# Sheet1.net
KiCad netlist of a schematic drawn in Altium Designer
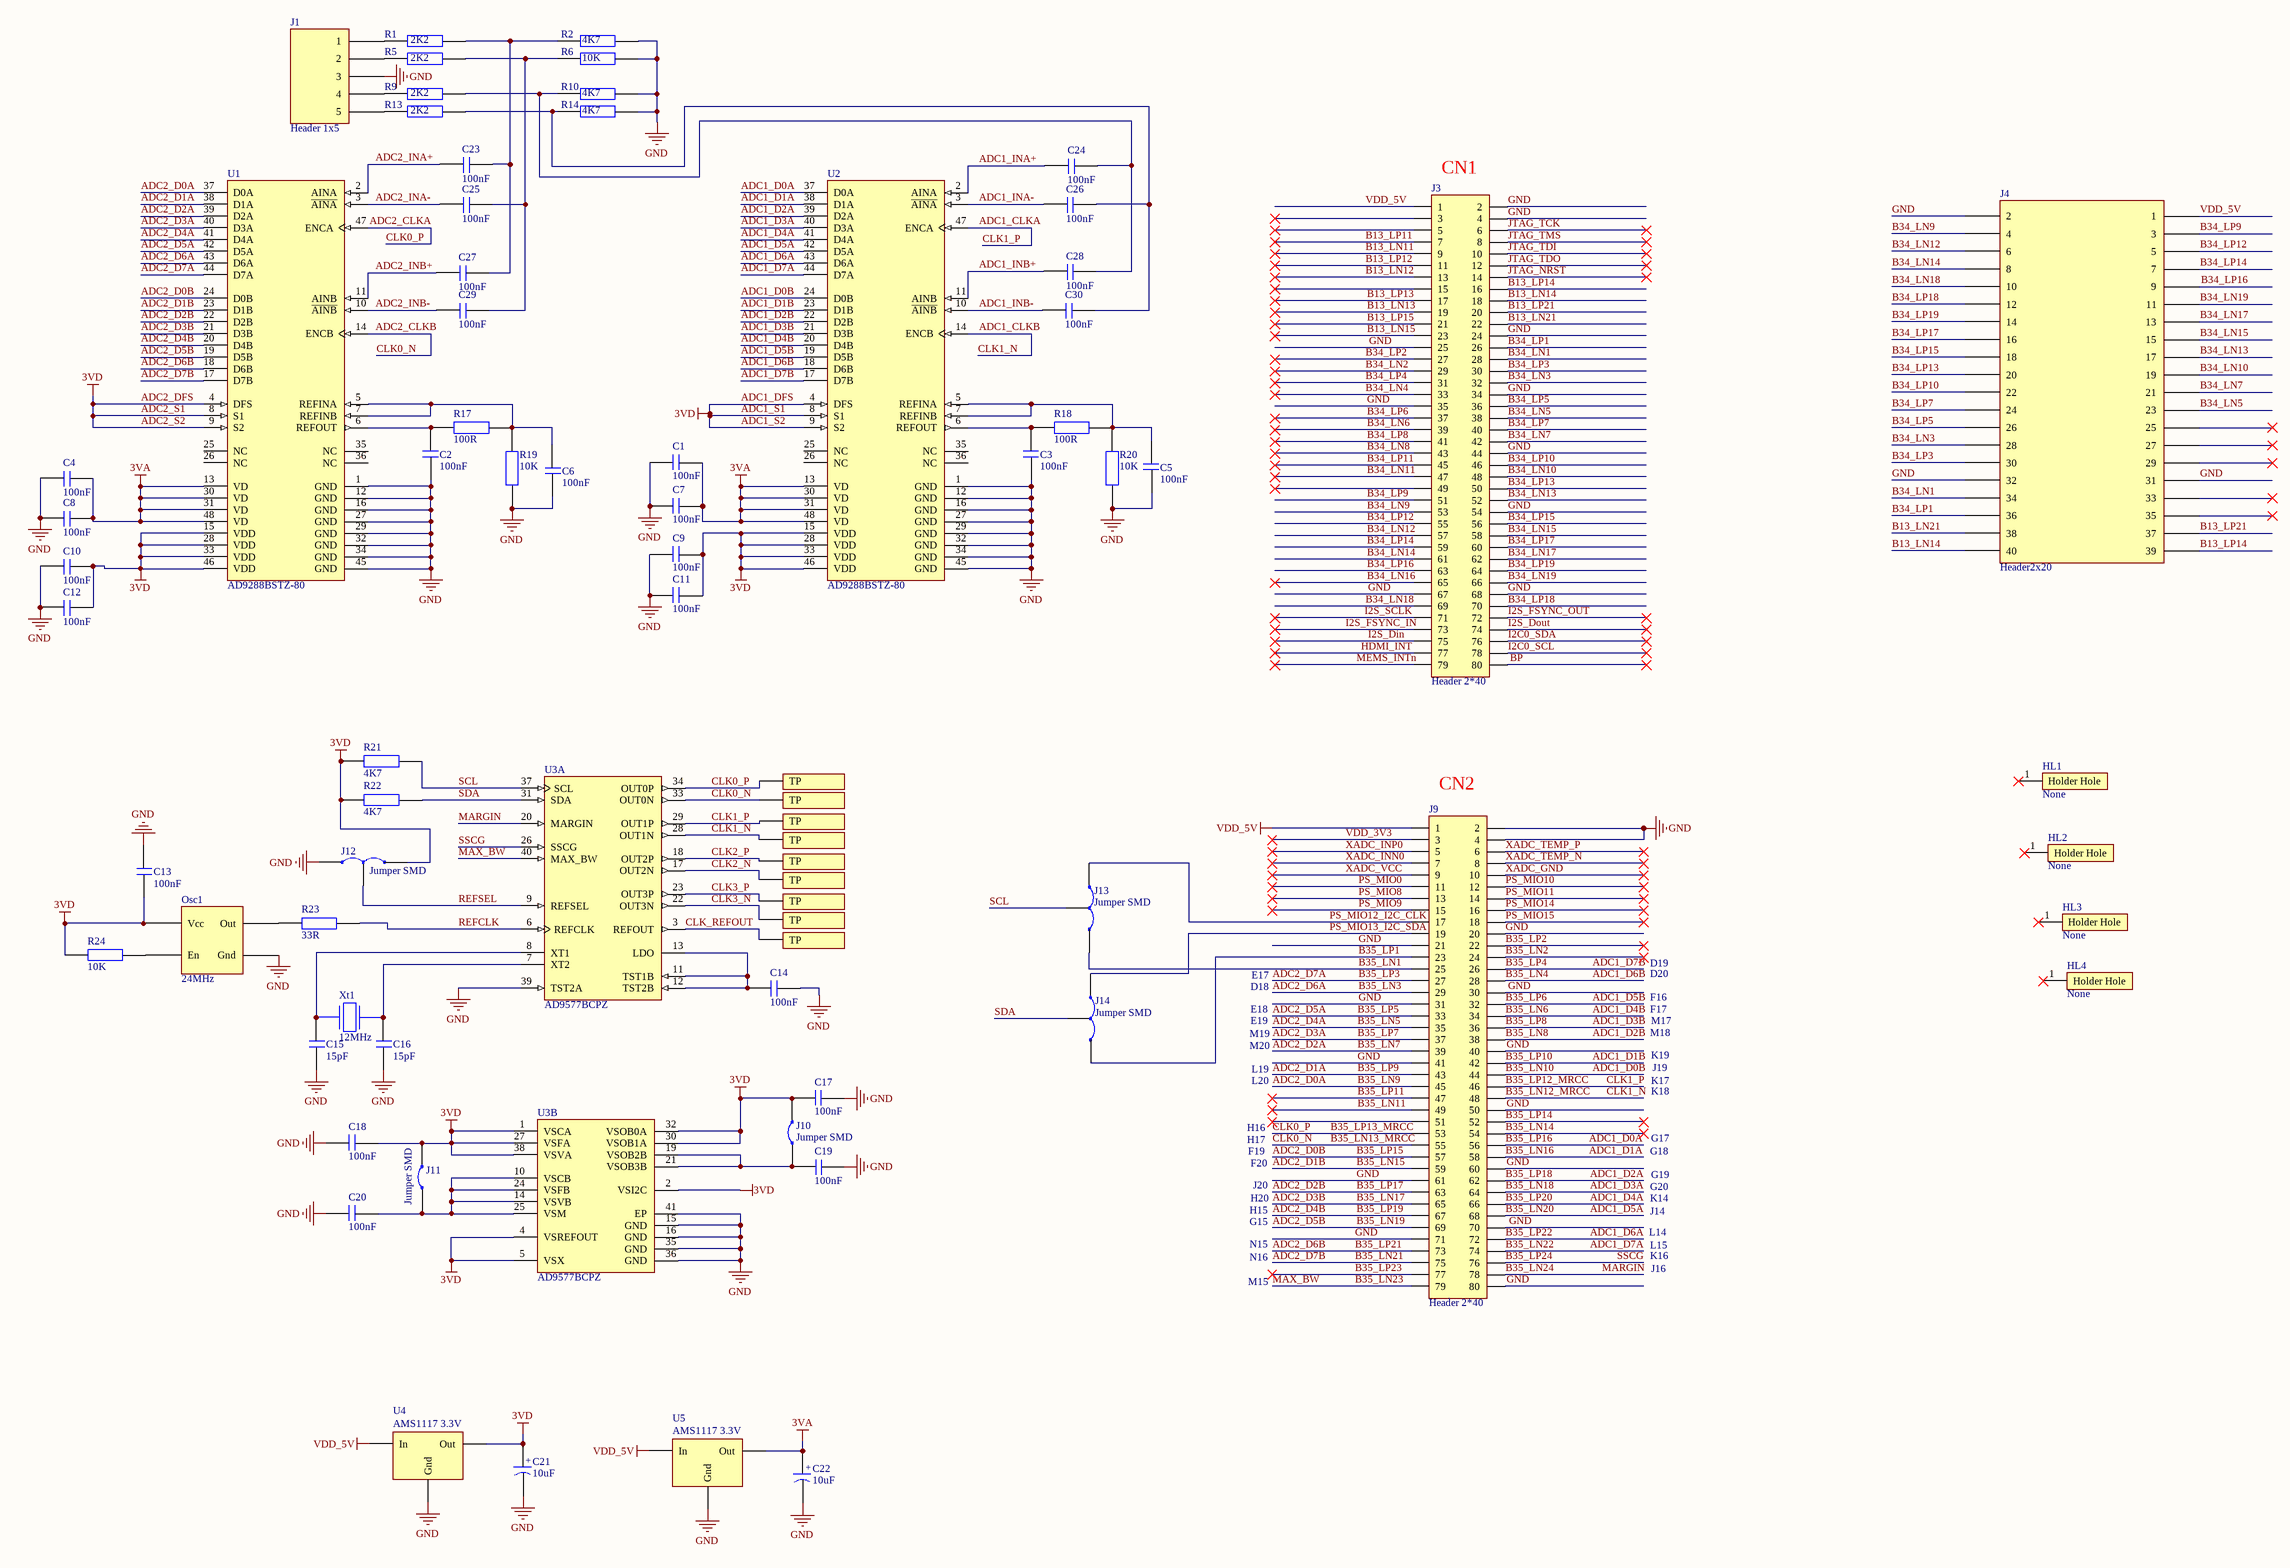
[diagram p0: Sheet1.SchDoc]

(export (version "E")
  (design (tool "Eeschema 10.0.6"))
  (components
    (comp (ref "C1")
      (value "100nF")
      (footprint "CAP_0805")
      (description "Capacitor SMD 0805")
      (libsource (lib "My_Integrated_Library") (part "Cap0805"))
    )
    (comp (ref "C2")
      (value "100nF")
      (footprint "CAP_0805")
      (description "Capacitor SMD 0805")
      (libsource (lib "My_Integrated_Library") (part "Cap0805"))
    )
    (comp (ref "C3")
      (value "100nF")
      (footprint "CAP_0805")
      (description "Capacitor SMD 0805")
      (libsource (lib "My_Integrated_Library") (part "Cap0805"))
    )
    (comp (ref "C4")
      (value "100nF")
      (footprint "CAP_0805")
      (description "Capacitor SMD 0805")
      (libsource (lib "My_Integrated_Library") (part "Cap0805"))
    )
    (comp (ref "C5")
      (value "100nF")
      (footprint "CAP_0805")
      (description "Capacitor SMD 0805")
      (libsource (lib "My_Integrated_Library") (part "Cap0805"))
    )
    (comp (ref "C6")
      (value "100nF")
      (footprint "CAP_0805")
      (description "Capacitor SMD 0805")
      (libsource (lib "My_Integrated_Library") (part "Cap0805"))
    )
    (comp (ref "C7")
      (value "100nF")
      (footprint "CAP_0805")
      (description "Capacitor SMD 0805")
      (libsource (lib "My_Integrated_Library") (part "Cap0805"))
    )
    (comp (ref "C8")
      (value "100nF")
      (footprint "CAP_0805")
      (description "Capacitor SMD 0805")
      (libsource (lib "My_Integrated_Library") (part "Cap0805"))
    )
    (comp (ref "C9")
      (value "100nF")
      (footprint "CAP_0805")
      (description "Capacitor SMD 0805")
      (libsource (lib "My_Integrated_Library") (part "Cap0805"))
    )
    (comp (ref "C10")
      (value "100nF")
      (footprint "CAP_0805")
      (description "Capacitor SMD 0805")
      (libsource (lib "My_Integrated_Library") (part "Cap0805"))
    )
    (comp (ref "C11")
      (value "100nF")
      (footprint "CAP_0805")
      (description "Capacitor SMD 0805")
      (libsource (lib "My_Integrated_Library") (part "Cap0805"))
    )
    (comp (ref "C12")
      (value "100nF")
      (footprint "CAP_0805")
      (description "Capacitor SMD 0805")
      (libsource (lib "My_Integrated_Library") (part "Cap0805"))
    )
    (comp (ref "C13")
      (value "100nF")
      (footprint "CAP_0805")
      (description "Capacitor SMD 0805")
      (libsource (lib "My_Integrated_Library") (part "Cap0805"))
    )
    (comp (ref "C14")
      (value "100nF")
      (footprint "CAP_0805")
      (description "Capacitor SMD 0805")
      (libsource (lib "My_Integrated_Library") (part "Cap0805"))
    )
    (comp (ref "C15")
      (value "15pF")
      (footprint "CAP_0805")
      (description "Capacitor SMD 0805")
      (libsource (lib "My_Integrated_Library") (part "Cap0805"))
    )
    (comp (ref "C16")
      (value "15pF")
      (footprint "CAP_0805")
      (description "Capacitor SMD 0805")
      (libsource (lib "My_Integrated_Library") (part "Cap0805"))
    )
    (comp (ref "C17")
      (value "100nF")
      (footprint "CAP_0805")
      (description "Capacitor SMD 0805")
      (libsource (lib "My_Integrated_Library") (part "Cap0805"))
    )
    (comp (ref "C18")
      (value "100nF")
      (footprint "CAP_0805")
      (description "Capacitor SMD 0805")
      (libsource (lib "My_Integrated_Library") (part "Cap0805"))
    )
    (comp (ref "C19")
      (value "100nF")
      (footprint "CAP_0805")
      (description "Capacitor SMD 0805")
      (libsource (lib "My_Integrated_Library") (part "Cap0805"))
    )
    (comp (ref "C20")
      (value "100nF")
      (footprint "CAP_0805")
      (description "Capacitor SMD 0805")
      (libsource (lib "My_Integrated_Library") (part "Cap0805"))
    )
    (comp (ref "C21")
      (value "10uF")
      (footprint "Cap_Tan_Size_B")
      (description "Capacitor SMD Tantalium Size B")
      (libsource (lib "My_Integrated_Library") (part "Cap_Tant_B"))
    )
    (comp (ref "C22")
      (value "10uF")
      (footprint "Cap_Tan_Size_B")
      (description "Capacitor SMD Tantalium Size B")
      (libsource (lib "My_Integrated_Library") (part "Cap_Tant_B"))
    )
    (comp (ref "C23")
      (value "100nF")
      (footprint "CAP_0805")
      (description "Capacitor SMD 0805")
      (libsource (lib "My_Integrated_Library") (part "Cap0805"))
    )
    (comp (ref "C24")
      (value "100nF")
      (footprint "CAP_0805")
      (description "Capacitor SMD 0805")
      (libsource (lib "My_Integrated_Library") (part "Cap0805"))
    )
    (comp (ref "C25")
      (value "100nF")
      (footprint "CAP_0805")
      (description "Capacitor SMD 0805")
      (libsource (lib "My_Integrated_Library") (part "Cap0805"))
    )
    (comp (ref "C26")
      (value "100nF")
      (footprint "CAP_0805")
      (description "Capacitor SMD 0805")
      (libsource (lib "My_Integrated_Library") (part "Cap0805"))
    )
    (comp (ref "C27")
      (value "100nF")
      (footprint "CAP_0805")
      (description "Capacitor SMD 0805")
      (libsource (lib "My_Integrated_Library") (part "Cap0805"))
    )
    (comp (ref "C28")
      (value "100nF")
      (footprint "CAP_0805")
      (description "Capacitor SMD 0805")
      (libsource (lib "My_Integrated_Library") (part "Cap0805"))
    )
    (comp (ref "C29")
      (value "100nF")
      (footprint "CAP_0805")
      (description "Capacitor SMD 0805")
      (libsource (lib "My_Integrated_Library") (part "Cap0805"))
    )
    (comp (ref "C30")
      (value "100nF")
      (footprint "CAP_0805")
      (description "Capacitor SMD 0805")
      (libsource (lib "My_Integrated_Library") (part "Cap0805"))
    )
    (comp (ref "HL1")
      (value "None")
      (footprint "Holder_hole")
      (description "PCB Holder Hole")
      (libsource (lib "My_Integrated_Library") (part "Holder_Hole"))
    )
    (comp (ref "HL2")
      (value "None")
      (footprint "Holder_hole")
      (description "PCB Holder Hole")
      (libsource (lib "My_Integrated_Library") (part "Holder_Hole"))
    )
    (comp (ref "HL3")
      (value "None")
      (footprint "Holder_hole")
      (description "PCB Holder Hole")
      (libsource (lib "My_Integrated_Library") (part "Holder_Hole"))
    )
    (comp (ref "HL4")
      (value "None")
      (footprint "Holder_hole")
      (description "PCB Holder Hole")
      (libsource (lib "My_Integrated_Library") (part "Holder_Hole"))
    )
    (comp (ref "J1")
      (value "Header 1x5")
      (footprint "Header_1x5")
      (description "Header 5-pin")
      (libsource (lib "My_Integrated_Library") (part "Header_1x5"))
    )
    (comp (ref "J3")
      (value "Header 2*40")
      (footprint "Header_2_40_1.27mm")
      (libsource (lib "My_Integrated_Library") (part "Header_2_40_1.27mm"))
    )
    (comp (ref "J4")
      (value "Header2x20")
      (footprint "Header_2x20_female")
      (description "Pin Header 2x20 pitch=2.54mm")
      (libsource (lib "My_Integrated_Library") (part "Header2x20"))
    )
    (comp (ref "J9")
      (value "Header 2*40")
      (footprint "Header_2_40_1.27mm")
      (libsource (lib "My_Integrated_Library") (part "Header_2_40_1.27mm"))
    )
    (comp (ref "J10")
      (value "Jumper SMD")
      (footprint "Jumper_smd")
      (libsource (lib "My_Integrated_Library") (part "Jump_smd"))
    )
    (comp (ref "J11")
      (value "Jumper SMD")
      (footprint "Jumper_smd")
      (libsource (lib "My_Integrated_Library") (part "Jump_smd"))
    )
    (comp (ref "J12")
      (value "Jumper SMD")
      (footprint "Jumper_smd_3pin")
      (libsource (lib "My_Integrated_Library") (part "Jump_smd_3tap"))
    )
    (comp (ref "J13")
      (value "Jumper SMD")
      (footprint "Jumper_smd_3pin")
      (libsource (lib "My_Integrated_Library") (part "Jump_smd_3tap"))
    )
    (comp (ref "J14")
      (value "Jumper SMD")
      (footprint "Jumper_smd_3pin")
      (libsource (lib "My_Integrated_Library") (part "Jump_smd_3tap"))
    )
    (comp (ref "Osc1")
      (value "24MHz")
      (footprint "Osc_SMD_5x7")
      (description "Oscillator SMD 5x7")
      (libsource (lib "My_Integrated_Library") (part "Osc_SMD"))
    )
    (comp (ref "R1")
      (value "2K2")
      (footprint "RES_0805")
      (description "Resistor SMD 0805")
      (libsource (lib "My_Integrated_Library") (part "Res0805"))
    )
    (comp (ref "R2")
      (value "4K7")
      (footprint "RES_0805")
      (description "Resistor SMD 0805")
      (libsource (lib "My_Integrated_Library") (part "Res0805"))
    )
    (comp (ref "R5")
      (value "2K2")
      (footprint "RES_0805")
      (description "Resistor SMD 0805")
      (libsource (lib "My_Integrated_Library") (part "Res0805"))
    )
    (comp (ref "R6")
      (value "10K")
      (footprint "RES_0805")
      (description "Resistor SMD 0805")
      (libsource (lib "My_Integrated_Library") (part "Res0805"))
    )
    (comp (ref "R9")
      (value "2K2")
      (footprint "RES_0805")
      (description "Resistor SMD 0805")
      (libsource (lib "My_Integrated_Library") (part "Res0805"))
    )
    (comp (ref "R10")
      (value "4K7")
      (footprint "RES_0805")
      (description "Resistor SMD 0805")
      (libsource (lib "My_Integrated_Library") (part "Res0805"))
    )
    (comp (ref "R13")
      (value "2K2")
      (footprint "RES_0805")
      (description "Resistor SMD 0805")
      (libsource (lib "My_Integrated_Library") (part "Res0805"))
    )
    (comp (ref "R14")
      (value "4K7")
      (footprint "RES_0805")
      (description "Resistor SMD 0805")
      (libsource (lib "My_Integrated_Library") (part "Res0805"))
    )
    (comp (ref "R17")
      (value "100R")
      (footprint "RES_0805")
      (description "Resistor SMD 0805")
      (libsource (lib "My_Integrated_Library") (part "Res0805"))
    )
    (comp (ref "R18")
      (value "100R")
      (footprint "RES_0805")
      (description "Resistor SMD 0805")
      (libsource (lib "My_Integrated_Library") (part "Res0805"))
    )
    (comp (ref "R19")
      (value "10K")
      (footprint "RES_0805")
      (description "Resistor SMD 0805")
      (libsource (lib "My_Integrated_Library") (part "Res0805"))
    )
    (comp (ref "R20")
      (value "10K")
      (footprint "RES_0805")
      (description "Resistor SMD 0805")
      (libsource (lib "My_Integrated_Library") (part "Res0805"))
    )
    (comp (ref "R21")
      (value "4K7")
      (footprint "RES_0805")
      (description "Resistor SMD 0805")
      (libsource (lib "My_Integrated_Library") (part "Res0805"))
    )
    (comp (ref "R22")
      (value "4K7")
      (footprint "RES_0805")
      (description "Resistor SMD 0805")
      (libsource (lib "My_Integrated_Library") (part "Res0805"))
    )
    (comp (ref "R23")
      (value "33R")
      (footprint "RES_0805")
      (description "Resistor SMD 0805")
      (libsource (lib "My_Integrated_Library") (part "Res0805"))
    )
    (comp (ref "R24")
      (value "10K")
      (footprint "RES_0805")
      (description "Resistor SMD 0805")
      (libsource (lib "My_Integrated_Library") (part "Res0805"))
    )
    (comp (ref "TP1")
      (value "TP")
      (footprint "TP")
      (description "Test point")
      (libsource (lib "My_Integrated_Library") (part "TP"))
    )
    (comp (ref "TP2")
      (value "TP")
      (footprint "TP")
      (description "Test point")
      (libsource (lib "My_Integrated_Library") (part "TP"))
    )
    (comp (ref "TP3")
      (value "TP")
      (footprint "TP")
      (description "Test point")
      (libsource (lib "My_Integrated_Library") (part "TP"))
    )
    (comp (ref "TP4")
      (value "TP")
      (footprint "TP")
      (description "Test point")
      (libsource (lib "My_Integrated_Library") (part "TP"))
    )
    (comp (ref "TP5")
      (value "TP")
      (footprint "TP")
      (description "Test point")
      (libsource (lib "My_Integrated_Library") (part "TP"))
    )
    (comp (ref "TP6")
      (value "TP")
      (footprint "TP")
      (description "Test point")
      (libsource (lib "My_Integrated_Library") (part "TP"))
    )
    (comp (ref "TP7")
      (value "TP")
      (footprint "TP")
      (description "Test point")
      (libsource (lib "My_Integrated_Library") (part "TP"))
    )
    (comp (ref "TP8")
      (value "TP")
      (footprint "TP")
      (description "Test point")
      (libsource (lib "My_Integrated_Library") (part "TP"))
    )
    (comp (ref "TP9")
      (value "TP")
      (footprint "TP")
      (description "Test point")
      (libsource (lib "My_Integrated_Library") (part "TP"))
    )
    (comp (ref "U1")
      (value "AD9288BSTZ-80")
      (footprint "LQFP-48Lead")
      (fields (field (name "GENERIC PART NUMBER") "AD9288-80") (field (name "MANUFACTURER") "Analog Devices"))
      (libsource (lib "My_Integrated_Library") (part "AD9288BSTZ-80"))
    )
    (comp (ref "U2")
      (value "AD9288BSTZ-80")
      (footprint "LQFP-48Lead")
      (fields (field (name "GENERIC PART NUMBER") "AD9288-80") (field (name "MANUFACTURER") "Analog Devices"))
      (libsource (lib "My_Integrated_Library") (part "AD9288BSTZ-80"))
    )
    (comp (ref "U3")
      (value "AD9577BCPZ")
      (footprint "LFCSP-40Lead")
      (fields (field (name "MANUFACTURER") "Analog Devices"))
      (libsource (lib "My_Integrated_Library") (part "AD9577BCPZ"))
    )
    (comp (ref "U4")
      (value "AMS1117 3.3V")
      (footprint "AMS1117-SOT223")
      (description "AMS1117 Regulator 3.3V SMD SOT223")
      (libsource (lib "My_Integrated_Library") (part "AMS1117-SOT223"))
    )
    (comp (ref "U5")
      (value "AMS1117 3.3V")
      (footprint "AMS1117-SOT223")
      (description "AMS1117 Regulator 3.3V SMD SOT223")
      (libsource (lib "My_Integrated_Library") (part "AMS1117-SOT223"))
    )
    (comp (ref "Xt1")
      (value "12MHz")
      (footprint "Xtal_SMD")
      (description "Crystal Oscillator SMD")
      (libsource (lib "My_Integrated_Library") (part "Xtal_SMD"))
    )
  )
  (nets
    (net (code "1") (name "/ADC1_CLKA") (class "Default")
      (node (ref "J9") (pin "46") (pinfunction "46_46") (pintype "passive"))
      (node (ref "TP3") (pin "1") (pinfunction "TP_1") (pintype "passive"))
      (node (ref "U2") (pin "47") (pinfunction "ENCA_47") (pintype "input"))
      (node (ref "U3") (pin "29") (pinfunction "OUT1P_29") (pintype "output"))
    )
    (net (code "2") (name "/ADC1_CLKB") (class "Default")
      (node (ref "J9") (pin "48") (pinfunction "48_48") (pintype "passive"))
      (node (ref "TP4") (pin "1") (pinfunction "TP_1") (pintype "passive"))
      (node (ref "U2") (pin "14") (pinfunction "ENCB_14") (pintype "input"))
      (node (ref "U3") (pin "28") (pinfunction "OUT1N_28") (pintype "output"))
    )
    (net (code "3") (name "/ADC1_D0A") (class "Default")
      (node (ref "J9") (pin "56") (pinfunction "56_56") (pintype "passive"))
      (node (ref "U2") (pin "37") (pinfunction "D0A_37") (pintype "tri_state"))
    )
    (net (code "4") (name "/ADC1_D0B") (class "Default")
      (node (ref "J9") (pin "44") (pinfunction "44_44") (pintype "passive"))
      (node (ref "U2") (pin "24") (pinfunction "D0B_24") (pintype "tri_state"))
    )
    (net (code "5") (name "/ADC1_D1A") (class "Default")
      (node (ref "J9") (pin "58") (pinfunction "58_58") (pintype "passive"))
      (node (ref "U2") (pin "38") (pinfunction "D1A_38") (pintype "tri_state"))
    )
    (net (code "6") (name "/ADC1_D1B") (class "Default")
      (node (ref "J9") (pin "42") (pinfunction "42_42") (pintype "passive"))
      (node (ref "U2") (pin "23") (pinfunction "D1B_23") (pintype "tri_state"))
    )
    (net (code "7") (name "/ADC1_D2A") (class "Default")
      (node (ref "J9") (pin "62") (pinfunction "62_62") (pintype "passive"))
      (node (ref "U2") (pin "39") (pinfunction "D2A_39") (pintype "tri_state"))
    )
    (net (code "8") (name "/ADC1_D2B") (class "Default")
      (node (ref "J9") (pin "38") (pinfunction "38_38") (pintype "passive"))
      (node (ref "U2") (pin "22") (pinfunction "D2B_22") (pintype "tri_state"))
    )
    (net (code "9") (name "/ADC1_D3A") (class "Default")
      (node (ref "J9") (pin "64") (pinfunction "64_64") (pintype "passive"))
      (node (ref "U2") (pin "40") (pinfunction "D3A_40") (pintype "tri_state"))
    )
    (net (code "10") (name "/ADC1_D3B") (class "Default")
      (node (ref "J9") (pin "36") (pinfunction "36_36") (pintype "passive"))
      (node (ref "U2") (pin "21") (pinfunction "D3B_21") (pintype "tri_state"))
    )
    (net (code "11") (name "/ADC1_D4A") (class "Default")
      (node (ref "J9") (pin "66") (pinfunction "66_66") (pintype "passive"))
      (node (ref "U2") (pin "41") (pinfunction "D4A_41") (pintype "tri_state"))
    )
    (net (code "12") (name "/ADC1_D4B") (class "Default")
      (node (ref "J9") (pin "34") (pinfunction "34_34") (pintype "passive"))
      (node (ref "U2") (pin "20") (pinfunction "D4B_20") (pintype "tri_state"))
    )
    (net (code "13") (name "/ADC1_D5A") (class "Default")
      (node (ref "J9") (pin "68") (pinfunction "68_68") (pintype "passive"))
      (node (ref "U2") (pin "42") (pinfunction "D5A_42") (pintype "tri_state"))
    )
    (net (code "14") (name "/ADC1_D5B") (class "Default")
      (node (ref "J9") (pin "32") (pinfunction "32_32") (pintype "passive"))
      (node (ref "U2") (pin "19") (pinfunction "D5B_19") (pintype "tri_state"))
    )
    (net (code "15") (name "/ADC1_D6A") (class "Default")
      (node (ref "J9") (pin "72") (pinfunction "72_72") (pintype "passive"))
      (node (ref "U2") (pin "43") (pinfunction "D6A_43") (pintype "tri_state"))
    )
    (net (code "16") (name "/ADC1_D6B") (class "Default")
      (node (ref "J9") (pin "28") (pinfunction "28_28") (pintype "passive"))
      (node (ref "U2") (pin "18") (pinfunction "D6B_18") (pintype "tri_state"))
    )
    (net (code "17") (name "/ADC1_D7A") (class "Default")
      (node (ref "J9") (pin "74") (pinfunction "74_74") (pintype "passive"))
      (node (ref "U2") (pin "44") (pinfunction "D7A_44") (pintype "tri_state"))
    )
    (net (code "18") (name "/ADC1_D7B") (class "Default")
      (node (ref "J9") (pin "26") (pinfunction "26_26") (pintype "passive"))
      (node (ref "U2") (pin "17") (pinfunction "D7B_17") (pintype "tri_state"))
    )
    (net (code "19") (name "/ADC1_INA+") (class "Default")
      (node (ref "C24") (pin "1") (pinfunction "1_1") (pintype "passive"))
      (node (ref "U2") (pin "2") (pinfunction "AINA_2") (pintype "input"))
    )
    (net (code "20") (name "/ADC1_INA-") (class "Default")
      (node (ref "C26") (pin "1") (pinfunction "1_1") (pintype "passive"))
      (node (ref "U2") (pin "3") (pinfunction "~{AINA}_3") (pintype "input"))
    )
    (net (code "21") (name "/ADC1_INB+") (class "Default")
      (node (ref "C28") (pin "1") (pinfunction "1_1") (pintype "passive"))
      (node (ref "U2") (pin "11") (pinfunction "AINB_11") (pintype "input"))
    )
    (net (code "22") (name "/ADC1_INB-") (class "Default")
      (node (ref "C30") (pin "1") (pinfunction "1_1") (pintype "passive"))
      (node (ref "U2") (pin "10") (pinfunction "~{AINB}_10") (pintype "input"))
    )
    (net (code "23") (name "/ADC2_CLKA") (class "Default")
      (node (ref "J9") (pin "53") (pinfunction "53_53") (pintype "passive"))
      (node (ref "TP1") (pin "1") (pinfunction "TP_1") (pintype "passive"))
      (node (ref "U1") (pin "47") (pinfunction "ENCA_47") (pintype "input"))
      (node (ref "U3") (pin "34") (pinfunction "OUT0P_34") (pintype "output"))
    )
    (net (code "24") (name "/ADC2_CLKB") (class "Default")
      (node (ref "J9") (pin "55") (pinfunction "55_55") (pintype "passive"))
      (node (ref "TP2") (pin "1") (pinfunction "TP_1") (pintype "passive"))
      (node (ref "U1") (pin "14") (pinfunction "ENCB_14") (pintype "input"))
      (node (ref "U3") (pin "33") (pinfunction "OUT0N_33") (pintype "output"))
    )
    (net (code "25") (name "/ADC2_D0A") (class "Default")
      (node (ref "J9") (pin "45") (pinfunction "45_45") (pintype "passive"))
      (node (ref "U1") (pin "37") (pinfunction "D0A_37") (pintype "tri_state"))
    )
    (net (code "26") (name "/ADC2_D0B") (class "Default")
      (node (ref "J9") (pin "57") (pinfunction "57_57") (pintype "passive"))
      (node (ref "U1") (pin "24") (pinfunction "D0B_24") (pintype "tri_state"))
    )
    (net (code "27") (name "/ADC2_D1A") (class "Default")
      (node (ref "J9") (pin "43") (pinfunction "43_43") (pintype "passive"))
      (node (ref "U1") (pin "38") (pinfunction "D1A_38") (pintype "tri_state"))
    )
    (net (code "28") (name "/ADC2_D1B") (class "Default")
      (node (ref "J9") (pin "59") (pinfunction "59_59") (pintype "passive"))
      (node (ref "U1") (pin "23") (pinfunction "D1B_23") (pintype "tri_state"))
    )
    (net (code "29") (name "/ADC2_D2A") (class "Default")
      (node (ref "J9") (pin "39") (pinfunction "39_39") (pintype "passive"))
      (node (ref "U1") (pin "39") (pinfunction "D2A_39") (pintype "tri_state"))
    )
    (net (code "30") (name "/ADC2_D2B") (class "Default")
      (node (ref "J9") (pin "63") (pinfunction "63_63") (pintype "passive"))
      (node (ref "U1") (pin "22") (pinfunction "D2B_22") (pintype "tri_state"))
    )
    (net (code "31") (name "/ADC2_D3A") (class "Default")
      (node (ref "J9") (pin "37") (pinfunction "37_37") (pintype "passive"))
      (node (ref "U1") (pin "40") (pinfunction "D3A_40") (pintype "tri_state"))
    )
    (net (code "32") (name "/ADC2_D3B") (class "Default")
      (node (ref "J9") (pin "65") (pinfunction "65_65") (pintype "passive"))
      (node (ref "U1") (pin "21") (pinfunction "D3B_21") (pintype "tri_state"))
    )
    (net (code "33") (name "/ADC2_D4A") (class "Default")
      (node (ref "J9") (pin "35") (pinfunction "35_35") (pintype "passive"))
      (node (ref "U1") (pin "41") (pinfunction "D4A_41") (pintype "tri_state"))
    )
    (net (code "34") (name "/ADC2_D4B") (class "Default")
      (node (ref "J9") (pin "67") (pinfunction "67_67") (pintype "passive"))
      (node (ref "U1") (pin "20") (pinfunction "D4B_20") (pintype "tri_state"))
    )
    (net (code "35") (name "/ADC2_D5A") (class "Default")
      (node (ref "J9") (pin "33") (pinfunction "33_33") (pintype "passive"))
      (node (ref "U1") (pin "42") (pinfunction "D5A_42") (pintype "tri_state"))
    )
    (net (code "36") (name "/ADC2_D5B") (class "Default")
      (node (ref "J9") (pin "69") (pinfunction "69_69") (pintype "passive"))
      (node (ref "U1") (pin "19") (pinfunction "D5B_19") (pintype "tri_state"))
    )
    (net (code "37") (name "/ADC2_D6A") (class "Default")
      (node (ref "J9") (pin "29") (pinfunction "29_29") (pintype "passive"))
      (node (ref "U1") (pin "43") (pinfunction "D6A_43") (pintype "tri_state"))
    )
    (net (code "38") (name "/ADC2_D6B") (class "Default")
      (node (ref "J9") (pin "73") (pinfunction "73_73") (pintype "passive"))
      (node (ref "U1") (pin "18") (pinfunction "D6B_18") (pintype "tri_state"))
    )
    (net (code "39") (name "/ADC2_D7A") (class "Default")
      (node (ref "J9") (pin "27") (pinfunction "27_27") (pintype "passive"))
      (node (ref "U1") (pin "44") (pinfunction "D7A_44") (pintype "tri_state"))
    )
    (net (code "40") (name "/ADC2_D7B") (class "Default")
      (node (ref "J9") (pin "75") (pinfunction "75_75") (pintype "passive"))
      (node (ref "U1") (pin "17") (pinfunction "D7B_17") (pintype "tri_state"))
    )
    (net (code "41") (name "/ADC2_INA+") (class "Default")
      (node (ref "C23") (pin "1") (pinfunction "1_1") (pintype "passive"))
      (node (ref "U1") (pin "2") (pinfunction "AINA_2") (pintype "input"))
    )
    (net (code "42") (name "/ADC2_INA-") (class "Default")
      (node (ref "C25") (pin "1") (pinfunction "1_1") (pintype "passive"))
      (node (ref "U1") (pin "3") (pinfunction "~{AINA}_3") (pintype "input"))
    )
    (net (code "43") (name "/ADC2_INB+") (class "Default")
      (node (ref "C27") (pin "1") (pinfunction "1_1") (pintype "passive"))
      (node (ref "U1") (pin "11") (pinfunction "AINB_11") (pintype "input"))
    )
    (net (code "44") (name "/ADC2_INB-") (class "Default")
      (node (ref "C29") (pin "1") (pinfunction "1_1") (pintype "passive"))
      (node (ref "U1") (pin "10") (pinfunction "~{AINB}_10") (pintype "input"))
    )
    (net (code "45") (name "/B13_LN11") (class "Default")
      (node (ref "J3") (pin "9") (pinfunction "9_9") (pintype "passive+no_connect"))
    )
    (net (code "46") (name "/B13_LN12") (class "Default")
      (node (ref "J3") (pin "13") (pinfunction "13_13") (pintype "passive+no_connect"))
    )
    (net (code "47") (name "/B13_LN13") (class "Default")
      (node (ref "J3") (pin "19") (pinfunction "19_19") (pintype "passive+no_connect"))
    )
    (net (code "48") (name "/B13_LN14") (class "Default")
      (node (ref "J3") (pin "18") (pinfunction "18_18") (pintype "passive"))
      (node (ref "J4") (pin "40") (pinfunction "40_40") (pintype "passive"))
    )
    (net (code "49") (name "/B13_LN15") (class "Default")
      (node (ref "J3") (pin "23") (pinfunction "23_23") (pintype "passive+no_connect"))
    )
    (net (code "50") (name "/B13_LN21") (class "Default")
      (node (ref "J3") (pin "22") (pinfunction "22_22") (pintype "passive"))
      (node (ref "J4") (pin "38") (pinfunction "38_38") (pintype "passive"))
    )
    (net (code "51") (name "/B13_LP11") (class "Default")
      (node (ref "J3") (pin "7") (pinfunction "7_7") (pintype "passive+no_connect"))
    )
    (net (code "52") (name "/B13_LP12") (class "Default")
      (node (ref "J3") (pin "11") (pinfunction "11_11") (pintype "passive+no_connect"))
    )
    (net (code "53") (name "/B13_LP13") (class "Default")
      (node (ref "J3") (pin "17") (pinfunction "17_17") (pintype "passive+no_connect"))
    )
    (net (code "54") (name "/B13_LP14") (class "Default")
      (node (ref "J3") (pin "16") (pinfunction "16_16") (pintype "passive"))
      (node (ref "J4") (pin "39") (pinfunction "39_39") (pintype "passive"))
    )
    (net (code "55") (name "/B13_LP15") (class "Default")
      (node (ref "J3") (pin "21") (pinfunction "21_21") (pintype "passive+no_connect"))
    )
    (net (code "56") (name "/B13_LP21") (class "Default")
      (node (ref "J3") (pin "20") (pinfunction "20_20") (pintype "passive"))
      (node (ref "J4") (pin "37") (pinfunction "37_37") (pintype "passive"))
    )
    (net (code "57") (name "/B34_LN1") (class "Default")
      (node (ref "J3") (pin "28") (pinfunction "28_28") (pintype "passive"))
      (node (ref "J4") (pin "34") (pinfunction "34_34") (pintype "passive"))
    )
    (net (code "58") (name "/B34_LN2") (class "Default")
      (node (ref "J3") (pin "29") (pinfunction "29_29") (pintype "passive+no_connect"))
    )
    (net (code "59") (name "/B34_LN3") (class "Default")
      (node (ref "J3") (pin "32") (pinfunction "32_32") (pintype "passive"))
      (node (ref "J4") (pin "28") (pinfunction "28_28") (pintype "passive"))
    )
    (net (code "60") (name "/B34_LN4") (class "Default")
      (node (ref "J3") (pin "33") (pinfunction "33_33") (pintype "passive+no_connect"))
    )
    (net (code "61") (name "/B34_LN5") (class "Default")
      (node (ref "J3") (pin "38") (pinfunction "38_38") (pintype "passive"))
      (node (ref "J4") (pin "23") (pinfunction "23_23") (pintype "passive"))
    )
    (net (code "62") (name "/B34_LN6") (class "Default")
      (node (ref "J3") (pin "39") (pinfunction "39_39") (pintype "passive+no_connect"))
    )
    (net (code "63") (name "/B34_LN7") (class "Default")
      (node (ref "J3") (pin "42") (pinfunction "42_42") (pintype "passive"))
      (node (ref "J4") (pin "21") (pinfunction "21_21") (pintype "passive"))
    )
    (net (code "64") (name "/B34_LN8") (class "Default")
      (node (ref "J3") (pin "43") (pinfunction "43_43") (pintype "passive+no_connect"))
    )
    (net (code "65") (name "/B34_LN9") (class "Default")
      (node (ref "J3") (pin "53") (pinfunction "53_53") (pintype "passive"))
      (node (ref "J4") (pin "4") (pinfunction "4_4") (pintype "passive"))
    )
    (net (code "66") (name "/B34_LN10") (class "Default")
      (node (ref "J3") (pin "48") (pinfunction "48_48") (pintype "passive"))
      (node (ref "J4") (pin "19") (pinfunction "19_19") (pintype "passive"))
    )
    (net (code "67") (name "/B34_LN11") (class "Default")
      (node (ref "J3") (pin "47") (pinfunction "47_47") (pintype "passive+no_connect"))
    )
    (net (code "68") (name "/B34_LN12") (class "Default")
      (node (ref "J3") (pin "57") (pinfunction "57_57") (pintype "passive"))
      (node (ref "J4") (pin "6") (pinfunction "6_6") (pintype "passive"))
    )
    (net (code "69") (name "/B34_LN13") (class "Default")
      (node (ref "J3") (pin "52") (pinfunction "52_52") (pintype "passive"))
      (node (ref "J4") (pin "17") (pinfunction "17_17") (pintype "passive"))
    )
    (net (code "70") (name "/B34_LN14") (class "Default")
      (node (ref "J3") (pin "61") (pinfunction "61_61") (pintype "passive"))
      (node (ref "J4") (pin "8") (pinfunction "8_8") (pintype "passive"))
    )
    (net (code "71") (name "/B34_LN15") (class "Default")
      (node (ref "J3") (pin "58") (pinfunction "58_58") (pintype "passive"))
      (node (ref "J4") (pin "15") (pinfunction "15_15") (pintype "passive"))
    )
    (net (code "72") (name "/B34_LN16") (class "Default")
      (node (ref "J3") (pin "65") (pinfunction "65_65") (pintype "passive+no_connect"))
    )
    (net (code "73") (name "/B34_LN17") (class "Default")
      (node (ref "J3") (pin "62") (pinfunction "62_62") (pintype "passive"))
      (node (ref "J4") (pin "13") (pinfunction "13_13") (pintype "passive"))
    )
    (net (code "74") (name "/B34_LN18") (class "Default")
      (node (ref "J3") (pin "69") (pinfunction "69_69") (pintype "passive"))
      (node (ref "J4") (pin "10") (pinfunction "10_10") (pintype "passive"))
    )
    (net (code "75") (name "/B34_LN19") (class "Default")
      (node (ref "J3") (pin "66") (pinfunction "66_66") (pintype "passive"))
      (node (ref "J4") (pin "11") (pinfunction "11_11") (pintype "passive"))
    )
    (net (code "76") (name "/B34_LP1") (class "Default")
      (node (ref "J3") (pin "26") (pinfunction "26_26") (pintype "passive"))
      (node (ref "J4") (pin "36") (pinfunction "36_36") (pintype "passive"))
    )
    (net (code "77") (name "/B34_LP2") (class "Default")
      (node (ref "J3") (pin "27") (pinfunction "27_27") (pintype "passive+no_connect"))
    )
    (net (code "78") (name "/B34_LP3") (class "Default")
      (node (ref "J3") (pin "30") (pinfunction "30_30") (pintype "passive"))
      (node (ref "J4") (pin "30") (pinfunction "30_30") (pintype "passive"))
    )
    (net (code "79") (name "/B34_LP4") (class "Default")
      (node (ref "J3") (pin "31") (pinfunction "31_31") (pintype "passive+no_connect"))
    )
    (net (code "80") (name "/B34_LP5") (class "Default")
      (node (ref "J3") (pin "36") (pinfunction "36_36") (pintype "passive"))
      (node (ref "J4") (pin "26") (pinfunction "26_26") (pintype "passive"))
    )
    (net (code "81") (name "/B34_LP6") (class "Default")
      (node (ref "J3") (pin "37") (pinfunction "37_37") (pintype "passive+no_connect"))
    )
    (net (code "82") (name "/B34_LP7") (class "Default")
      (node (ref "J3") (pin "40") (pinfunction "40_40") (pintype "passive"))
      (node (ref "J4") (pin "24") (pinfunction "24_24") (pintype "passive"))
    )
    (net (code "83") (name "/B34_LP8") (class "Default")
      (node (ref "J3") (pin "41") (pinfunction "41_41") (pintype "passive+no_connect"))
    )
    (net (code "84") (name "/B34_LP9") (class "Default")
      (node (ref "J3") (pin "51") (pinfunction "51_51") (pintype "passive"))
      (node (ref "J4") (pin "3") (pinfunction "3_3") (pintype "passive"))
    )
    (net (code "85") (name "/B34_LP10") (class "Default")
      (node (ref "J3") (pin "46") (pinfunction "46_46") (pintype "passive"))
      (node (ref "J4") (pin "22") (pinfunction "22_22") (pintype "passive"))
    )
    (net (code "86") (name "/B34_LP11") (class "Default")
      (node (ref "J3") (pin "45") (pinfunction "45_45") (pintype "passive+no_connect"))
    )
    (net (code "87") (name "/B34_LP12") (class "Default")
      (node (ref "J3") (pin "55") (pinfunction "55_55") (pintype "passive"))
      (node (ref "J4") (pin "5") (pinfunction "5_5") (pintype "passive"))
    )
    (net (code "88") (name "/B34_LP13") (class "Default")
      (node (ref "J3") (pin "50") (pinfunction "50_50") (pintype "passive"))
      (node (ref "J4") (pin "20") (pinfunction "20_20") (pintype "passive"))
    )
    (net (code "89") (name "/B34_LP14") (class "Default")
      (node (ref "J3") (pin "59") (pinfunction "59_59") (pintype "passive"))
      (node (ref "J4") (pin "7") (pinfunction "7_7") (pintype "passive"))
    )
    (net (code "90") (name "/B34_LP15") (class "Default")
      (node (ref "J3") (pin "56") (pinfunction "56_56") (pintype "passive"))
      (node (ref "J4") (pin "18") (pinfunction "18_18") (pintype "passive"))
    )
    (net (code "91") (name "/B34_LP16") (class "Default")
      (node (ref "J3") (pin "63") (pinfunction "63_63") (pintype "passive"))
      (node (ref "J4") (pin "9") (pinfunction "9_9") (pintype "passive"))
    )
    (net (code "92") (name "/B34_LP17") (class "Default")
      (node (ref "J3") (pin "60") (pinfunction "60_60") (pintype "passive"))
      (node (ref "J4") (pin "16") (pinfunction "16_16") (pintype "passive"))
    )
    (net (code "93") (name "/B34_LP18") (class "Default")
      (node (ref "J3") (pin "70") (pinfunction "70_70") (pintype "passive"))
      (node (ref "J4") (pin "12") (pinfunction "12_12") (pintype "passive"))
    )
    (net (code "94") (name "/B34_LP19") (class "Default")
      (node (ref "J3") (pin "64") (pinfunction "64_64") (pintype "passive"))
      (node (ref "J4") (pin "14") (pinfunction "14_14") (pintype "passive"))
    )
    (net (code "95") (name "/B35_LN1") (class "Default")
      (node (ref "J13") (pin "3") (pinfunction "3_3") (pintype "passive"))
      (node (ref "J9") (pin "25") (pinfunction "25_25") (pintype "passive"))
    )
    (net (code "96") (name "/B35_LN2") (class "Default")
      (node (ref "J9") (pin "24") (pinfunction "24_24") (pintype "passive+no_connect"))
    )
    (net (code "97") (name "/B35_LN11") (class "Default")
      (node (ref "J9") (pin "49") (pinfunction "49_49") (pintype "passive+no_connect"))
    )
    (net (code "98") (name "/B35_LN14") (class "Default")
      (node (ref "J9") (pin "54") (pinfunction "54_54") (pintype "passive+no_connect"))
    )
    (net (code "99") (name "/B35_LN23") (class "Default")
      (node (ref "J9") (pin "79") (pinfunction "79_79") (pintype "passive"))
      (node (ref "U3") (pin "40") (pinfunction "MAX_BW_40") (pintype "input"))
    )
    (net (code "100") (name "/B35_LN24") (class "Default")
      (node (ref "J9") (pin "78") (pinfunction "78_78") (pintype "passive"))
      (node (ref "U3") (pin "20") (pinfunction "MARGIN_20") (pintype "input"))
    )
    (net (code "101") (name "/B35_LP1") (class "Default")
      (node (ref "J14") (pin "3") (pinfunction "3_3") (pintype "passive"))
      (node (ref "J9") (pin "23") (pinfunction "23_23") (pintype "passive"))
    )
    (net (code "102") (name "/B35_LP2") (class "Default")
      (node (ref "J9") (pin "22") (pinfunction "22_22") (pintype "passive+no_connect"))
    )
    (net (code "103") (name "/B35_LP11") (class "Default")
      (node (ref "J9") (pin "47") (pinfunction "47_47") (pintype "passive+no_connect"))
    )
    (net (code "104") (name "/B35_LP14") (class "Default")
      (node (ref "J9") (pin "52") (pinfunction "52_52") (pintype "passive+no_connect"))
    )
    (net (code "105") (name "/B35_LP23") (class "Default")
      (node (ref "J9") (pin "77") (pinfunction "77_77") (pintype "passive+no_connect"))
    )
    (net (code "106") (name "/B35_LP24") (class "Default")
      (node (ref "J9") (pin "76") (pinfunction "76_76") (pintype "passive"))
      (node (ref "U3") (pin "26") (pinfunction "SSCG_26") (pintype "input"))
    )
    (net (code "107") (name "/BP") (class "Default")
      (node (ref "J3") (pin "80") (pinfunction "80_80") (pintype "passive+no_connect"))
    )
    (net (code "108") (name "/CLK2_N") (class "Default")
      (node (ref "TP6") (pin "1") (pinfunction "TP_1") (pintype "passive"))
      (node (ref "U3") (pin "17") (pinfunction "OUT2N_17") (pintype "output"))
    )
    (net (code "109") (name "/CLK2_P") (class "Default")
      (node (ref "TP5") (pin "1") (pinfunction "TP_1") (pintype "passive"))
      (node (ref "U3") (pin "18") (pinfunction "OUT2P_18") (pintype "output"))
    )
    (net (code "110") (name "/CLK3_N") (class "Default")
      (node (ref "TP8") (pin "1") (pinfunction "TP_1") (pintype "passive"))
      (node (ref "U3") (pin "22") (pinfunction "OUT3N_22") (pintype "output"))
    )
    (net (code "111") (name "/CLK3_P") (class "Default")
      (node (ref "TP7") (pin "1") (pinfunction "TP_1") (pintype "passive"))
      (node (ref "U3") (pin "23") (pinfunction "OUT3P_23") (pintype "output"))
    )
    (net (code "112") (name "/CLK_REFOUT") (class "Default")
      (node (ref "TP9") (pin "1") (pinfunction "TP_1") (pintype "passive"))
      (node (ref "U3") (pin "3") (pinfunction "REFOUT_3") (pintype "output"))
    )
    (net (code "113") (name "/HDMI_INT") (class "Default")
      (node (ref "J3") (pin "77") (pinfunction "77_77") (pintype "passive+no_connect"))
    )
    (net (code "114") (name "/I2C0_SCL") (class "Default")
      (node (ref "J3") (pin "78") (pinfunction "78_78") (pintype "passive+no_connect"))
    )
    (net (code "115") (name "/I2C0_SDA") (class "Default")
      (node (ref "J3") (pin "76") (pinfunction "76_76") (pintype "passive+no_connect"))
    )
    (net (code "116") (name "/I2S_Din") (class "Default")
      (node (ref "J3") (pin "75") (pinfunction "75_75") (pintype "passive+no_connect"))
    )
    (net (code "117") (name "/I2S_Dout") (class "Default")
      (node (ref "J3") (pin "74") (pinfunction "74_74") (pintype "passive+no_connect"))
    )
    (net (code "118") (name "/I2S_FSYNC_IN") (class "Default")
      (node (ref "J3") (pin "73") (pinfunction "73_73") (pintype "passive+no_connect"))
    )
    (net (code "119") (name "/I2S_FSYNC_OUT") (class "Default")
      (node (ref "J3") (pin "72") (pinfunction "72_72") (pintype "passive+no_connect"))
    )
    (net (code "120") (name "/I2S_SCLK") (class "Default")
      (node (ref "J3") (pin "71") (pinfunction "71_71") (pintype "passive+no_connect"))
    )
    (net (code "121") (name "/JTAG_NRST") (class "Default")
      (node (ref "J3") (pin "14") (pinfunction "14_14") (pintype "passive+no_connect"))
    )
    (net (code "122") (name "/JTAG_TCK") (class "Default")
      (node (ref "J3") (pin "6") (pinfunction "6_6") (pintype "passive+no_connect"))
    )
    (net (code "123") (name "/JTAG_TDI") (class "Default")
      (node (ref "J3") (pin "10") (pinfunction "10_10") (pintype "passive+no_connect"))
    )
    (net (code "124") (name "/JTAG_TDO") (class "Default")
      (node (ref "J3") (pin "12") (pinfunction "12_12") (pintype "passive+no_connect"))
    )
    (net (code "125") (name "/JTAG_TMS") (class "Default")
      (node (ref "J3") (pin "8") (pinfunction "8_8") (pintype "passive+no_connect"))
    )
    (net (code "126") (name "/MEMS_INTn") (class "Default")
      (node (ref "J3") (pin "79") (pinfunction "79_79") (pintype "passive+no_connect"))
    )
    (net (code "127") (name "/PS_MIO0") (class "Default")
      (node (ref "J9") (pin "11") (pinfunction "11_11") (pintype "passive+no_connect"))
    )
    (net (code "128") (name "/PS_MIO8") (class "Default")
      (node (ref "J9") (pin "13") (pinfunction "13_13") (pintype "passive+no_connect"))
    )
    (net (code "129") (name "/PS_MIO9") (class "Default")
      (node (ref "J9") (pin "15") (pinfunction "15_15") (pintype "passive+no_connect"))
    )
    (net (code "130") (name "/PS_MIO10") (class "Default")
      (node (ref "J9") (pin "12") (pinfunction "12_12") (pintype "passive+no_connect"))
    )
    (net (code "131") (name "/PS_MIO11") (class "Default")
      (node (ref "J9") (pin "14") (pinfunction "14_14") (pintype "passive+no_connect"))
    )
    (net (code "132") (name "/PS_MIO12_I2C_CLK") (class "Default")
      (node (ref "J13") (pin "1") (pinfunction "1_1") (pintype "passive"))
      (node (ref "J9") (pin "17") (pinfunction "17_17") (pintype "passive"))
    )
    (net (code "133") (name "/PS_MIO13_I2C_SDA") (class "Default")
      (node (ref "J14") (pin "1") (pinfunction "1_1") (pintype "passive"))
      (node (ref "J9") (pin "19") (pinfunction "19_19") (pintype "passive"))
    )
    (net (code "134") (name "/PS_MIO14") (class "Default")
      (node (ref "J9") (pin "16") (pinfunction "16_16") (pintype "passive+no_connect"))
    )
    (net (code "135") (name "/PS_MIO15") (class "Default")
      (node (ref "J9") (pin "18") (pinfunction "18_18") (pintype "passive+no_connect"))
    )
    (net (code "136") (name "/REFCLK") (class "Default")
      (node (ref "R23") (pin "2") (pinfunction "2_2") (pintype "passive"))
      (node (ref "U3") (pin "6") (pinfunction "REFCLK_6") (pintype "input"))
    )
    (net (code "137") (name "/REFSEL") (class "Default")
      (node (ref "J12") (pin "2") (pinfunction "2_2") (pintype "passive"))
      (node (ref "U3") (pin "9") (pinfunction "REFSEL_9") (pintype "input"))
    )
    (net (code "138") (name "/SCL") (class "Default")
      (node (ref "J13") (pin "2") (pinfunction "2_2") (pintype "passive"))
      (node (ref "R21") (pin "2") (pinfunction "2_2") (pintype "passive"))
      (node (ref "U3") (pin "37") (pinfunction "SCL_37") (pintype "input"))
    )
    (net (code "139") (name "/SDA") (class "Default")
      (node (ref "J14") (pin "2") (pinfunction "2_2") (pintype "passive"))
      (node (ref "R22") (pin "2") (pinfunction "2_2") (pintype "passive"))
      (node (ref "U3") (pin "31") (pinfunction "SDA_31") (pintype "input"))
    )
    (net (code "140") (name "/VDD_3V3") (class "Default")
      (node (ref "J9") (pin "3") (pinfunction "3_3") (pintype "passive+no_connect"))
    )
    (net (code "141") (name "/XADC_GND") (class "Default")
      (node (ref "J9") (pin "10") (pinfunction "10_10") (pintype "passive+no_connect"))
    )
    (net (code "142") (name "/XADC_INN0") (class "Default")
      (node (ref "J9") (pin "7") (pinfunction "7_7") (pintype "passive+no_connect"))
    )
    (net (code "143") (name "/XADC_INP0") (class "Default")
      (node (ref "J9") (pin "5") (pinfunction "5_5") (pintype "passive+no_connect"))
    )
    (net (code "144") (name "/XADC_TEMP_N") (class "Default")
      (node (ref "J9") (pin "8") (pinfunction "8_8") (pintype "passive+no_connect"))
    )
    (net (code "145") (name "/XADC_TEMP_P") (class "Default")
      (node (ref "J9") (pin "6") (pinfunction "6_6") (pintype "passive+no_connect"))
    )
    (net (code "146") (name "/XADC_VCC") (class "Default")
      (node (ref "J9") (pin "9") (pinfunction "9_9") (pintype "passive+no_connect"))
    )
    (net (code "147") (name "3VA") (class "Default")
      (node (ref "C1") (pin "1") (pinfunction "1_1") (pintype "passive"))
      (node (ref "C22") (pin "+") (pinfunction "+_+") (pintype "passive"))
      (node (ref "C4") (pin "2") (pinfunction "2_2") (pintype "passive"))
      (node (ref "C7") (pin "1") (pinfunction "1_1") (pintype "passive"))
      (node (ref "C8") (pin "2") (pinfunction "2_2") (pintype "passive"))
      (node (ref "U1") (pin "13") (pinfunction "VD_13") (pintype "power_in"))
      (node (ref "U1") (pin "30") (pinfunction "VD_30") (pintype "power_in"))
      (node (ref "U1") (pin "31") (pinfunction "VD_31") (pintype "power_in"))
      (node (ref "U1") (pin "48") (pinfunction "VD_48") (pintype "power_in"))
      (node (ref "U2") (pin "13") (pinfunction "VD_13") (pintype "power_in"))
      (node (ref "U2") (pin "30") (pinfunction "VD_30") (pintype "power_in"))
      (node (ref "U2") (pin "31") (pinfunction "VD_31") (pintype "power_in"))
      (node (ref "U2") (pin "48") (pinfunction "VD_48") (pintype "power_in"))
      (node (ref "U5") (pin "3") (pinfunction "Out_3") (pintype "passive"))
    )
    (net (code "148") (name "3VD") (class "Default")
      (node (ref "C10") (pin "2") (pinfunction "2_2") (pintype "passive"))
      (node (ref "C11") (pin "1") (pinfunction "1_1") (pintype "passive"))
      (node (ref "C12") (pin "2") (pinfunction "2_2") (pintype "passive"))
      (node (ref "C13") (pin "1") (pinfunction "1_1") (pintype "passive"))
      (node (ref "C17") (pin "2") (pinfunction "2_2") (pintype "passive"))
      (node (ref "C18") (pin "1") (pinfunction "1_1") (pintype "passive"))
      (node (ref "C21") (pin "+") (pinfunction "+_+") (pintype "passive"))
      (node (ref "C9") (pin "1") (pinfunction "1_1") (pintype "passive"))
      (node (ref "J10") (pin "1") (pinfunction "1_1") (pintype "passive"))
      (node (ref "J11") (pin "1") (pinfunction "1_1") (pintype "passive"))
      (node (ref "J12") (pin "3") (pinfunction "3_3") (pintype "passive"))
      (node (ref "Osc1") (pin "1") (pinfunction "Vcc_1") (pintype "passive"))
      (node (ref "R21") (pin "1") (pinfunction "1_1") (pintype "passive"))
      (node (ref "R22") (pin "1") (pinfunction "1_1") (pintype "passive"))
      (node (ref "R24") (pin "2") (pinfunction "2_2") (pintype "passive"))
      (node (ref "U1") (pin "15") (pinfunction "VDD_15") (pintype "power_in"))
      (node (ref "U1") (pin "28") (pinfunction "VDD_28") (pintype "power_in"))
      (node (ref "U1") (pin "33") (pinfunction "VDD_33") (pintype "power_in"))
      (node (ref "U1") (pin "4") (pinfunction "DFS_4") (pintype "input"))
      (node (ref "U1") (pin "46") (pinfunction "VDD_46") (pintype "power_in"))
      (node (ref "U1") (pin "8") (pinfunction "S1_8") (pintype "input"))
      (node (ref "U1") (pin "9") (pinfunction "S2_9") (pintype "input"))
      (node (ref "U2") (pin "15") (pinfunction "VDD_15") (pintype "power_in"))
      (node (ref "U2") (pin "28") (pinfunction "VDD_28") (pintype "power_in"))
      (node (ref "U2") (pin "33") (pinfunction "VDD_33") (pintype "power_in"))
      (node (ref "U2") (pin "4") (pinfunction "DFS_4") (pintype "input"))
      (node (ref "U2") (pin "46") (pinfunction "VDD_46") (pintype "power_in"))
      (node (ref "U2") (pin "8") (pinfunction "S1_8") (pintype "input"))
      (node (ref "U2") (pin "9") (pinfunction "S2_9") (pintype "input"))
      (node (ref "U3") (pin "1") (pinfunction "VSCA_1") (pintype "power_in"))
      (node (ref "U3") (pin "2") (pinfunction "VSI2C_2") (pintype "power_in"))
      (node (ref "U3") (pin "27") (pinfunction "VSFA_27") (pintype "power_in"))
      (node (ref "U3") (pin "30") (pinfunction "VSOB1A_30") (pintype "power_in"))
      (node (ref "U3") (pin "32") (pinfunction "VSOB0A_32") (pintype "power_in"))
      (node (ref "U3") (pin "38") (pinfunction "VSVA_38") (pintype "power_in"))
      (node (ref "U3") (pin "4") (pinfunction "VSREFOUT_4") (pintype "power_in"))
      (node (ref "U3") (pin "5") (pinfunction "VSX_5") (pintype "power_in"))
      (node (ref "U4") (pin "3") (pinfunction "Out_3") (pintype "passive"))
    )
    (net (code "149") (name "GND") (class "Default")
      (node (ref "C1") (pin "2") (pinfunction "2_2") (pintype "passive"))
      (node (ref "C10") (pin "1") (pinfunction "1_1") (pintype "passive"))
      (node (ref "C11") (pin "2") (pinfunction "2_2") (pintype "passive"))
      (node (ref "C12") (pin "1") (pinfunction "1_1") (pintype "passive"))
      (node (ref "C13") (pin "2") (pinfunction "2_2") (pintype "passive"))
      (node (ref "C14") (pin "2") (pinfunction "2_2") (pintype "passive"))
      (node (ref "C15") (pin "1") (pinfunction "1_1") (pintype "passive"))
      (node (ref "C16") (pin "1") (pinfunction "1_1") (pintype "passive"))
      (node (ref "C17") (pin "1") (pinfunction "1_1") (pintype "passive"))
      (node (ref "C18") (pin "2") (pinfunction "2_2") (pintype "passive"))
      (node (ref "C19") (pin "2") (pinfunction "2_2") (pintype "passive"))
      (node (ref "C2") (pin "2") (pinfunction "2_2") (pintype "passive"))
      (node (ref "C20") (pin "2") (pinfunction "2_2") (pintype "passive"))
      (node (ref "C21") (pin "-") (pinfunction "-_-") (pintype "passive"))
      (node (ref "C22") (pin "-") (pinfunction "-_-") (pintype "passive"))
      (node (ref "C3") (pin "2") (pinfunction "2_2") (pintype "passive"))
      (node (ref "C4") (pin "1") (pinfunction "1_1") (pintype "passive"))
      (node (ref "C5") (pin "2") (pinfunction "2_2") (pintype "passive"))
      (node (ref "C6") (pin "1") (pinfunction "1_1") (pintype "passive"))
      (node (ref "C7") (pin "2") (pinfunction "2_2") (pintype "passive"))
      (node (ref "C8") (pin "1") (pinfunction "1_1") (pintype "passive"))
      (node (ref "C9") (pin "2") (pinfunction "2_2") (pintype "passive"))
      (node (ref "J1") (pin "3") (pinfunction "3_3") (pintype "passive"))
      (node (ref "J12") (pin "1") (pinfunction "1_1") (pintype "passive"))
      (node (ref "J3") (pin "2") (pinfunction "2_2") (pintype "passive"))
      (node (ref "J3") (pin "24") (pinfunction "24_24") (pintype "passive"))
      (node (ref "J3") (pin "25") (pinfunction "25_25") (pintype "passive"))
      (node (ref "J3") (pin "34") (pinfunction "34_34") (pintype "passive"))
      (node (ref "J3") (pin "35") (pinfunction "35_35") (pintype "passive"))
      (node (ref "J3") (pin "4") (pinfunction "4_4") (pintype "passive"))
      (node (ref "J3") (pin "44") (pinfunction "44_44") (pintype "passive"))
      (node (ref "J3") (pin "54") (pinfunction "54_54") (pintype "passive"))
      (node (ref "J3") (pin "67") (pinfunction "67_67") (pintype "passive"))
      (node (ref "J3") (pin "68") (pinfunction "68_68") (pintype "passive"))
      (node (ref "J4") (pin "2") (pinfunction "2_2") (pintype "passive"))
      (node (ref "J4") (pin "31") (pinfunction "31_31") (pintype "passive"))
      (node (ref "J4") (pin "32") (pinfunction "32_32") (pintype "passive"))
      (node (ref "J9") (pin "2") (pinfunction "2_2") (pintype "passive"))
      (node (ref "J9") (pin "20") (pinfunction "20_20") (pintype "passive"))
      (node (ref "J9") (pin "21") (pinfunction "21_21") (pintype "passive"))
      (node (ref "J9") (pin "30") (pinfunction "30_30") (pintype "passive"))
      (node (ref "J9") (pin "31") (pinfunction "31_31") (pintype "passive"))
      (node (ref "J9") (pin "4") (pinfunction "4_4") (pintype "passive"))
      (node (ref "J9") (pin "40") (pinfunction "40_40") (pintype "passive"))
      (node (ref "J9") (pin "41") (pinfunction "41_41") (pintype "passive"))
      (node (ref "J9") (pin "50") (pinfunction "50_50") (pintype "passive"))
      (node (ref "J9") (pin "60") (pinfunction "60_60") (pintype "passive"))
      (node (ref "J9") (pin "61") (pinfunction "61_61") (pintype "passive"))
      (node (ref "J9") (pin "70") (pinfunction "70_70") (pintype "passive"))
      (node (ref "J9") (pin "71") (pinfunction "71_71") (pintype "passive"))
      (node (ref "J9") (pin "80") (pinfunction "80_80") (pintype "passive"))
      (node (ref "Osc1") (pin "4") (pinfunction "Gnd_4") (pintype "passive"))
      (node (ref "R10") (pin "2") (pinfunction "2_2") (pintype "passive"))
      (node (ref "R14") (pin "2") (pinfunction "2_2") (pintype "passive"))
      (node (ref "R19") (pin "2") (pinfunction "2_2") (pintype "passive"))
      (node (ref "R2") (pin "2") (pinfunction "2_2") (pintype "passive"))
      (node (ref "R20") (pin "2") (pinfunction "2_2") (pintype "passive"))
      (node (ref "R6") (pin "2") (pinfunction "2_2") (pintype "passive"))
      (node (ref "U1") (pin "1") (pinfunction "GND_1") (pintype "power_in"))
      (node (ref "U1") (pin "12") (pinfunction "GND_12") (pintype "power_in"))
      (node (ref "U1") (pin "16") (pinfunction "GND_16") (pintype "power_in"))
      (node (ref "U1") (pin "27") (pinfunction "GND_27") (pintype "power_in"))
      (node (ref "U1") (pin "29") (pinfunction "GND_29") (pintype "power_in"))
      (node (ref "U1") (pin "32") (pinfunction "GND_32") (pintype "power_in"))
      (node (ref "U1") (pin "34") (pinfunction "GND_34") (pintype "power_in"))
      (node (ref "U1") (pin "45") (pinfunction "GND_45") (pintype "power_in"))
      (node (ref "U2") (pin "1") (pinfunction "GND_1") (pintype "power_in"))
      (node (ref "U2") (pin "12") (pinfunction "GND_12") (pintype "power_in"))
      (node (ref "U2") (pin "16") (pinfunction "GND_16") (pintype "power_in"))
      (node (ref "U2") (pin "27") (pinfunction "GND_27") (pintype "power_in"))
      (node (ref "U2") (pin "29") (pinfunction "GND_29") (pintype "power_in"))
      (node (ref "U2") (pin "32") (pinfunction "GND_32") (pintype "power_in"))
      (node (ref "U2") (pin "34") (pinfunction "GND_34") (pintype "power_in"))
      (node (ref "U2") (pin "45") (pinfunction "GND_45") (pintype "power_in"))
      (node (ref "U3") (pin "15") (pinfunction "GND_15") (pintype "power_in"))
      (node (ref "U3") (pin "16") (pinfunction "GND_16") (pintype "power_in"))
      (node (ref "U3") (pin "35") (pinfunction "GND_35") (pintype "power_in"))
      (node (ref "U3") (pin "36") (pinfunction "GND_36") (pintype "power_in"))
      (node (ref "U3") (pin "39") (pinfunction "TST2A_39") (pintype "input"))
      (node (ref "U3") (pin "41") (pinfunction "EP_41") (pintype "power_in"))
      (node (ref "U4") (pin "2") (pinfunction "Gnd_2") (pintype "passive"))
      (node (ref "U5") (pin "2") (pinfunction "Gnd_2") (pintype "passive"))
    )
    (net (code "150") (name "Net-(C23-Pad2)") (class "Default")
      (node (ref "C23") (pin "2") (pinfunction "2_2") (pintype "passive"))
      (node (ref "C27") (pin "2") (pinfunction "2_2") (pintype "passive"))
      (node (ref "R1") (pin "2") (pinfunction "2_2") (pintype "passive"))
      (node (ref "R2") (pin "1") (pinfunction "1_1") (pintype "passive"))
    )
    (net (code "151") (name "Net-(C24-Pad2)") (class "Default")
      (node (ref "C24") (pin "2") (pinfunction "2_2") (pintype "passive"))
      (node (ref "C28") (pin "2") (pinfunction "2_2") (pintype "passive"))
      (node (ref "R10") (pin "1") (pinfunction "1_1") (pintype "passive"))
      (node (ref "R9") (pin "2") (pinfunction "2_2") (pintype "passive"))
    )
    (net (code "152") (name "Net-(C25-Pad2)") (class "Default")
      (node (ref "C25") (pin "2") (pinfunction "2_2") (pintype "passive"))
      (node (ref "C29") (pin "2") (pinfunction "2_2") (pintype "passive"))
      (node (ref "R5") (pin "2") (pinfunction "2_2") (pintype "passive"))
      (node (ref "R6") (pin "1") (pinfunction "1_1") (pintype "passive"))
    )
    (net (code "153") (name "Net-(C26-Pad2)") (class "Default")
      (node (ref "C26") (pin "2") (pinfunction "2_2") (pintype "passive"))
      (node (ref "C30") (pin "2") (pinfunction "2_2") (pintype "passive"))
      (node (ref "R13") (pin "2") (pinfunction "2_2") (pintype "passive"))
      (node (ref "R14") (pin "1") (pinfunction "1_1") (pintype "passive"))
    )
    (net (code "154") (name "Net-(J1-Pad1)") (class "Default")
      (node (ref "J1") (pin "1") (pinfunction "1_1") (pintype "passive"))
      (node (ref "R1") (pin "1") (pinfunction "1_1") (pintype "passive"))
    )
    (net (code "155") (name "Net-(J1-Pad2)") (class "Default")
      (node (ref "J1") (pin "2") (pinfunction "2_2") (pintype "passive"))
      (node (ref "R5") (pin "1") (pinfunction "1_1") (pintype "passive"))
    )
    (net (code "156") (name "Net-(J1-Pad4)") (class "Default")
      (node (ref "J1") (pin "4") (pinfunction "4_4") (pintype "passive"))
      (node (ref "R9") (pin "1") (pinfunction "1_1") (pintype "passive"))
    )
    (net (code "157") (name "Net-(J1-Pad5)") (class "Default")
      (node (ref "J1") (pin "5") (pinfunction "5_5") (pintype "passive"))
      (node (ref "R13") (pin "1") (pinfunction "1_1") (pintype "passive"))
    )
    (net (code "158") (name "Net-(Osc1-En)") (class "Default")
      (node (ref "Osc1") (pin "2") (pinfunction "En_2") (pintype "passive"))
      (node (ref "R24") (pin "1") (pinfunction "1_1") (pintype "passive"))
    )
    (net (code "159") (name "Net-(Osc1-Out)") (class "Default")
      (node (ref "Osc1") (pin "3") (pinfunction "Out_3") (pintype "passive"))
      (node (ref "R23") (pin "1") (pinfunction "1_1") (pintype "passive"))
    )
    (net (code "160") (name "Net-(U1-REFINA)") (class "Default")
      (node (ref "C6") (pin "2") (pinfunction "2_2") (pintype "passive"))
      (node (ref "R17") (pin "2") (pinfunction "2_2") (pintype "passive"))
      (node (ref "R19") (pin "1") (pinfunction "1_1") (pintype "passive"))
      (node (ref "U1") (pin "5") (pinfunction "REFINA_5") (pintype "input"))
      (node (ref "U1") (pin "7") (pinfunction "REFINB_7") (pintype "input"))
    )
    (net (code "161") (name "Net-(U1-REFOUT)") (class "Default")
      (node (ref "C2") (pin "1") (pinfunction "1_1") (pintype "passive"))
      (node (ref "R17") (pin "1") (pinfunction "1_1") (pintype "passive"))
      (node (ref "U1") (pin "6") (pinfunction "REFOUT_6") (pintype "output"))
    )
    (net (code "162") (name "Net-(U2-REFINA)") (class "Default")
      (node (ref "C5") (pin "1") (pinfunction "1_1") (pintype "passive"))
      (node (ref "R18") (pin "1") (pinfunction "1_1") (pintype "passive"))
      (node (ref "R20") (pin "1") (pinfunction "1_1") (pintype "passive"))
      (node (ref "U2") (pin "5") (pinfunction "REFINA_5") (pintype "input"))
      (node (ref "U2") (pin "7") (pinfunction "REFINB_7") (pintype "input"))
    )
    (net (code "163") (name "Net-(U2-REFOUT)") (class "Default")
      (node (ref "C3") (pin "1") (pinfunction "1_1") (pintype "passive"))
      (node (ref "R18") (pin "2") (pinfunction "2_2") (pintype "passive"))
      (node (ref "U2") (pin "6") (pinfunction "REFOUT_6") (pintype "output"))
    )
    (net (code "164") (name "Net-(U3A-LDO)") (class "Default")
      (node (ref "C14") (pin "1") (pinfunction "1_1") (pintype "passive"))
      (node (ref "U3") (pin "11") (pinfunction "TST1B_11") (pintype "input"))
      (node (ref "U3") (pin "12") (pinfunction "TST2B_12") (pintype "input"))
      (node (ref "U3") (pin "13") (pinfunction "LDO_13") (pintype "passive"))
    )
    (net (code "165") (name "Net-(U3A-XT1)") (class "Default")
      (node (ref "C15") (pin "2") (pinfunction "2_2") (pintype "passive"))
      (node (ref "U3") (pin "8") (pinfunction "XT1_8") (pintype "passive"))
      (node (ref "Xt1") (pin "2") (pinfunction "2_2") (pintype "passive"))
    )
    (net (code "166") (name "Net-(U3A-XT2)") (class "Default")
      (node (ref "C16") (pin "2") (pinfunction "2_2") (pintype "passive"))
      (node (ref "U3") (pin "7") (pinfunction "XT2_7") (pintype "passive"))
      (node (ref "Xt1") (pin "1") (pinfunction "1_1") (pintype "passive"))
    )
    (net (code "167") (name "Net-(U3B-VSCB)") (class "Default")
      (node (ref "C20") (pin "1") (pinfunction "1_1") (pintype "passive"))
      (node (ref "J11") (pin "2") (pinfunction "2_2") (pintype "passive"))
      (node (ref "U3") (pin "10") (pinfunction "VSCB_10") (pintype "power_in"))
      (node (ref "U3") (pin "14") (pinfunction "VSVB_14") (pintype "power_in"))
      (node (ref "U3") (pin "24") (pinfunction "VSFB_24") (pintype "power_in"))
      (node (ref "U3") (pin "25") (pinfunction "VSM_25") (pintype "power_in"))
    )
    (net (code "168") (name "Net-(U3B-VSOB2B)") (class "Default")
      (node (ref "C19") (pin "1") (pinfunction "1_1") (pintype "passive"))
      (node (ref "J10") (pin "2") (pinfunction "2_2") (pintype "passive"))
      (node (ref "U3") (pin "19") (pinfunction "VSOB2B_19") (pintype "power_in"))
      (node (ref "U3") (pin "21") (pinfunction "VSOB3B_21") (pintype "power_in"))
    )
    (net (code "169") (name "VDD_5V") (class "Default")
      (node (ref "J3") (pin "1") (pinfunction "1_1") (pintype "passive"))
      (node (ref "J4") (pin "1") (pinfunction "1_1") (pintype "passive"))
      (node (ref "J9") (pin "1") (pinfunction "1_1") (pintype "passive"))
      (node (ref "U4") (pin "1") (pinfunction "In_1") (pintype "passive"))
      (node (ref "U5") (pin "1") (pinfunction "In_1") (pintype "passive"))
    )
    (net (code "170") (name "unconnected-(HL1-Holder_Hole-Pad1)") (class "Default")
      (node (ref "HL1") (pin "1") (pinfunction "Holder_Hole_1") (pintype "passive+no_connect"))
    )
    (net (code "171") (name "unconnected-(HL2-Holder_Hole-Pad1)") (class "Default")
      (node (ref "HL2") (pin "1") (pinfunction "Holder_Hole_1") (pintype "passive+no_connect"))
    )
    (net (code "172") (name "unconnected-(HL3-Holder_Hole-Pad1)") (class "Default")
      (node (ref "HL3") (pin "1") (pinfunction "Holder_Hole_1") (pintype "passive+no_connect"))
    )
    (net (code "173") (name "unconnected-(HL4-Holder_Hole-Pad1)") (class "Default")
      (node (ref "HL4") (pin "1") (pinfunction "Holder_Hole_1") (pintype "passive+no_connect"))
    )
    (net (code "174") (name "unconnected-(J3-Pad3)") (class "Default")
      (node (ref "J3") (pin "3") (pinfunction "3_3") (pintype "passive+no_connect"))
    )
    (net (code "175") (name "unconnected-(J3-Pad5)") (class "Default")
      (node (ref "J3") (pin "5") (pinfunction "5_5") (pintype "passive+no_connect"))
    )
    (net (code "176") (name "unconnected-(J3-Pad15)") (class "Default")
      (node (ref "J3") (pin "15") (pinfunction "15_15") (pintype "passive+no_connect"))
    )
    (net (code "177") (name "unconnected-(J3-Pad49)") (class "Default")
      (node (ref "J3") (pin "49") (pinfunction "49_49") (pintype "passive+no_connect"))
    )
    (net (code "178") (name "unconnected-(J4-Pad25)") (class "Default")
      (node (ref "J4") (pin "25") (pinfunction "25_25") (pintype "passive+no_connect"))
    )
    (net (code "179") (name "unconnected-(J4-Pad27)") (class "Default")
      (node (ref "J4") (pin "27") (pinfunction "27_27") (pintype "passive+no_connect"))
    )
    (net (code "180") (name "unconnected-(J4-Pad29)") (class "Default")
      (node (ref "J4") (pin "29") (pinfunction "29_29") (pintype "passive+no_connect"))
    )
    (net (code "181") (name "unconnected-(J4-Pad33)") (class "Default")
      (node (ref "J4") (pin "33") (pinfunction "33_33") (pintype "passive+no_connect"))
    )
    (net (code "182") (name "unconnected-(J4-Pad35)") (class "Default")
      (node (ref "J4") (pin "35") (pinfunction "35_35") (pintype "passive+no_connect"))
    )
    (net (code "183") (name "unconnected-(J9-Pad51)") (class "Default")
      (node (ref "J9") (pin "51") (pinfunction "51_51") (pintype "passive+no_connect"))
    )
    (net (code "184") (name "unconnected-(U1-NC-Pad25)") (class "Default")
      (node (ref "U1") (pin "25") (pinfunction "NC_25") (pintype "passive"))
    )
    (net (code "185") (name "unconnected-(U1-NC-Pad26)") (class "Default")
      (node (ref "U1") (pin "26") (pinfunction "NC_26") (pintype "passive"))
    )
    (net (code "186") (name "unconnected-(U1-NC-Pad35)") (class "Default")
      (node (ref "U1") (pin "35") (pinfunction "NC_35") (pintype "passive"))
    )
    (net (code "187") (name "unconnected-(U1-NC-Pad36)") (class "Default")
      (node (ref "U1") (pin "36") (pinfunction "NC_36") (pintype "passive"))
    )
    (net (code "188") (name "unconnected-(U2-NC-Pad25)") (class "Default")
      (node (ref "U2") (pin "25") (pinfunction "NC_25") (pintype "passive"))
    )
    (net (code "189") (name "unconnected-(U2-NC-Pad26)") (class "Default")
      (node (ref "U2") (pin "26") (pinfunction "NC_26") (pintype "passive"))
    )
    (net (code "190") (name "unconnected-(U2-NC-Pad35)") (class "Default")
      (node (ref "U2") (pin "35") (pinfunction "NC_35") (pintype "passive"))
    )
    (net (code "191") (name "unconnected-(U2-NC-Pad36)") (class "Default")
      (node (ref "U2") (pin "36") (pinfunction "NC_36") (pintype "passive"))
    )
  )
)
